# OnStep_Box_SCH.net
KiCad netlist of a schematic drawn in EAGLE
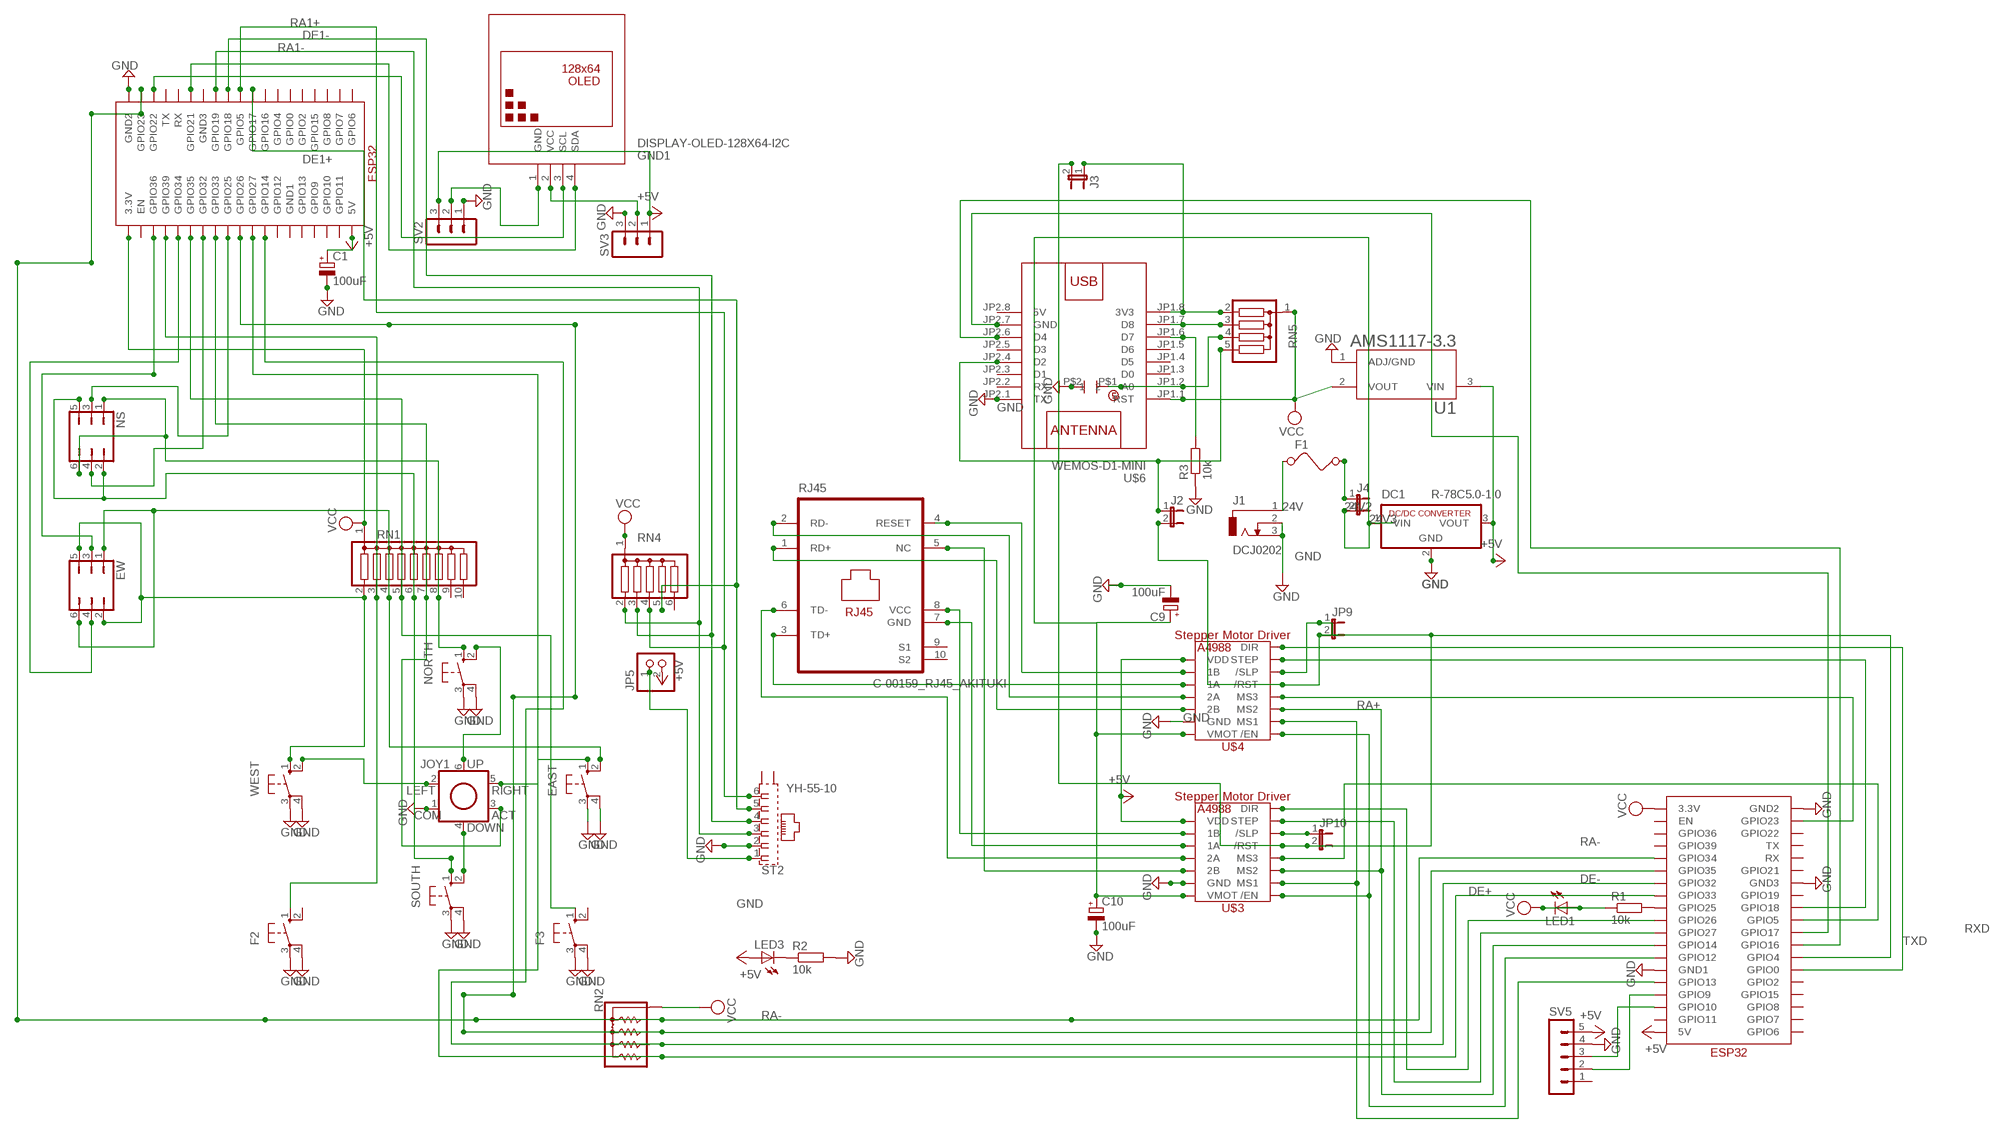
[diagram p0: schematic, sheet 1]

(export (version "E")
  (design (tool "Eeschema 10.0.6"))
  (components
    (comp (ref "C1")
      (value "100uF")
      (footprint "eagle-import:E2-4")
      (libsource (lib "eagle-import") (part "CPOL-EUE2-4"))
    )
    (comp (ref "C9")
      (value "100uF")
      (footprint "eagle-import:E2-5")
      (libsource (lib "eagle-import") (part "rcl_334_CPOL-EUE2-5"))
    )
    (comp (ref "C10")
      (value "100uF")
      (footprint "eagle-import:E2-5")
      (libsource (lib "eagle-import") (part "rcl_334_CPOL-EUE2-5"))
    )
    (comp (ref "CERAMIC_CAPACITOR1")
      (value "CERAMIC_CAPACITOR")
      (footprint "eagle-import:CERAMIC_CAPACITOR")
      (libsource (lib "eagle-import") (part "CERAMIC_CAPACITOR"))
    )
    (comp (ref "DC1")
      (value "R-78C5.0-1.0")
      (footprint "eagle-import:SIP3")
      (libsource (lib "eagle-import") (part "R-78C-1.05.0"))
    )
    (comp (ref "EAST")
      (value "40-XX")
      (footprint "eagle-import:B3F-40XX")
      (fields (field (name "MF") "OMRON COMPONENTS USA") (field (name "MPN") "B3F-4000"))
      (libsource (lib "eagle-import") (part "40-XX"))
    )
    (comp (ref "EW")
      (value "JP3Q")
      (footprint "eagle-import:JP3Q")
      (libsource (lib "eagle-import") (part "JP3Q"))
    )
    (comp (ref "F1")
      (value "FUSE")
      (footprint "eagle-import:FUSE")
      (libsource (lib "eagle-import") (part "FUSE"))
    )
    (comp (ref "F2")
      (value "10-XX")
      (footprint "eagle-import:B3F-10XX")
      (fields (field (name "MPN") "B3F-1000"))
      (libsource (lib "eagle-import") (part "10-XX"))
    )
    (comp (ref "F3")
      (value "10-XX")
      (footprint "eagle-import:B3F-10XX")
      (fields (field (name "MPN") "B3F-1000"))
      (libsource (lib "eagle-import") (part "10-XX"))
    )
    (comp (ref "GND1")
      (value "DISPLAY-OLED-128X64-I2C")
      (footprint "eagle-import:DISPLAY-OLED-128X64-I2C")
      (libsource (lib "eagle-import") (part "DISPLAY-OLED-128X64-I2C"))
    )
    (comp (ref "J1")
      (value "DCJ0202")
      (footprint "eagle-import:DCJ0202")
      (libsource (lib "eagle-import") (part "DCJ0202"))
    )
    (comp (ref "J2")
      (value "JP1E")
      (footprint "eagle-import:JP1")
      (libsource (lib "eagle-import") (part "JP1E"))
    )
    (comp (ref "J3")
      (value "JP1E")
      (footprint "eagle-import:JP1")
      (libsource (lib "eagle-import") (part "JP1E"))
    )
    (comp (ref "J4")
      (value "JP1E")
      (footprint "eagle-import:JP1")
      (libsource (lib "eagle-import") (part "JP1E"))
    )
    (comp (ref "JOY1")
      (value "JOYSTICK")
      (footprint "eagle-import:JOYSTICK")
      (libsource (lib "eagle-import") (part "JOYSTICK"))
    )
    (comp (ref "JP5")
      (value "PINHD-1X2")
      (footprint "eagle-import:1X02")
      (libsource (lib "eagle-import") (part "PINHD-1X2"))
    )
    (comp (ref "JP9")
      (value "JP1E")
      (footprint "eagle-import:JP1")
      (libsource (lib "eagle-import") (part "JP1E"))
    )
    (comp (ref "JP10")
      (value "JP1E")
      (footprint "eagle-import:JP1")
      (libsource (lib "eagle-import") (part "JP1E"))
    )
    (comp (ref "LED1")
      (value "LEDSFH480")
      (footprint "eagle-import:SFH480")
      (libsource (lib "eagle-import") (part "LEDSFH480"))
    )
    (comp (ref "LED3")
      (value "LEDSFH480")
      (footprint "eagle-import:SFH480")
      (libsource (lib "eagle-import") (part "LEDSFH480"))
    )
    (comp (ref "NORTH")
      (value "40-XX")
      (footprint "eagle-import:B3F-40XX")
      (fields (field (name "MF") "OMRON COMPONENTS USA") (field (name "MPN") "B3F-4000"))
      (libsource (lib "eagle-import") (part "40-XX"))
    )
    (comp (ref "NS")
      (value "JP3Q")
      (footprint "eagle-import:JP3Q")
      (libsource (lib "eagle-import") (part "JP3Q"))
    )
    (comp (ref "R1")
      (value "10k")
      (footprint "eagle-import:0204_5")
      (libsource (lib "eagle-import") (part "R-EU_0204/5"))
    )
    (comp (ref "R2")
      (value "10k")
      (footprint "eagle-import:0204_5")
      (libsource (lib "eagle-import") (part "R-EU_0204/5"))
    )
    (comp (ref "R3")
      (value "10k")
      (footprint "eagle-import:0204_5")
      (libsource (lib "eagle-import") (part "R-EU_0204/5"))
    )
    (comp (ref "RJ45")
      (value "C-00159_RJ45_AKITUKI")
      (footprint "eagle-import:PJ-J0")
      (libsource (lib "eagle-import") (part "C-00159_RJ45_AKITUKI"))
    )
    (comp (ref "RN1")
      (value "G09R")
      (footprint "eagle-import:SIL10")
      (libsource (lib "eagle-import") (part "G09R"))
    )
    (comp (ref "RN2")
      (value "4605X")
      (footprint "eagle-import:SIP5")
      (libsource (lib "eagle-import") (part "4605X"))
    )
    (comp (ref "RN4")
      (value "G05R")
      (footprint "eagle-import:SIL6")
      (libsource (lib "eagle-import") (part "G05R"))
    )
    (comp (ref "RN5")
      (value "G04R")
      (footprint "eagle-import:SIL5")
      (libsource (lib "eagle-import") (part "G04R"))
    )
    (comp (ref "SOUTH")
      (value "40-XX")
      (footprint "eagle-import:B3F-40XX")
      (fields (field (name "MF") "OMRON COMPONENTS USA") (field (name "MPN") "B3F-4000"))
      (libsource (lib "eagle-import") (part "40-XX"))
    )
    (comp (ref "ST2")
      (value "YH-55-10")
      (footprint "eagle-import:YH-55-10")
      (libsource (lib "eagle-import") (part "YH-55-10"))
    )
    (comp (ref "SV2")
      (value "MA03-1")
      (footprint "eagle-import:MA03-1")
      (libsource (lib "eagle-import") (part "MA03-1"))
    )
    (comp (ref "SV3")
      (value "MA03-1")
      (footprint "eagle-import:MA03-1")
      (libsource (lib "eagle-import") (part "MA03-1"))
    )
    (comp (ref "SV5")
      (value "MA05-1")
      (footprint "eagle-import:MA05-1")
      (libsource (lib "eagle-import") (part "MA05-1"))
    )
    (comp (ref "U$1")
      (value "ESP32")
      (footprint "eagle-import:ESP32")
      (libsource (lib "eagle-import") (part "ESP32"))
    )
    (comp (ref "U$3")
      (value "A4988_STEP")
      (footprint "eagle-import:A4988_STEP")
      (libsource (lib "eagle-import") (part "A4988_STEP"))
    )
    (comp (ref "U$4")
      (value "A4988_STEP")
      (footprint "eagle-import:A4988_STEP")
      (libsource (lib "eagle-import") (part "A4988_STEP"))
    )
    (comp (ref "U$6")
      (value "WEMOS-D1-MINI")
      (footprint "eagle-import:WEMOS-D1-MINI")
      (libsource (lib "eagle-import") (part "WEMOS-D1-MINI"))
    )
    (comp (ref "U$7")
      (value "ESP32")
      (footprint "eagle-import:ESP32")
      (libsource (lib "eagle-import") (part "ESP32"))
    )
    (comp (ref "U1")
      (value "AMS1117-3.3")
      (footprint "eagle-import:SOT229P700X180-4N")
      (fields (field (name "MF") "Advanced Monolithic Systems"))
      (libsource (lib "eagle-import") (part "AMS1117-3.3"))
    )
    (comp (ref "WEST")
      (value "40-XX")
      (footprint "eagle-import:B3F-40XX")
      (fields (field (name "MF") "OMRON COMPONENTS USA") (field (name "MPN") "B3F-4000"))
      (libsource (lib "eagle-import") (part "40-XX"))
    )
  )
  (nets
    (net (code "1") (name "+5V") (class "Default")
      (node (ref "C1") (pin "+") (pinfunction "+_+") (pintype "passive"))
      (node (ref "DC1") (pin "3") (pinfunction "VOUT_3") (pintype "passive"))
      (node (ref "JP5") (pin "2") (pinfunction "2_2") (pintype "passive"))
      (node (ref "LED3") (pin "A") (pinfunction "A_A") (pintype "passive"))
      (node (ref "SV2") (pin "3") (pinfunction "3_3") (pintype "passive"))
      (node (ref "SV3") (pin "1") (pinfunction "1_1") (pintype "passive"))
      (node (ref "SV5") (pin "5") (pinfunction "5_5") (pintype "passive"))
      (node (ref "U$1") (pin "5V") (pinfunction "5V_5V") (pintype "bidirectional"))
      (node (ref "U$3") (pin "VDD") (pinfunction "VDD_VDD") (pintype "bidirectional"))
      (node (ref "U$4") (pin "VDD") (pinfunction "VDD_VDD") (pintype "bidirectional"))
      (node (ref "U$7") (pin "5V") (pinfunction "5V_5V") (pintype "bidirectional"))
      (node (ref "U1") (pin "3") (pinfunction "VIN_3") (pintype "input"))
    )
    (net (code "2") (name "/5V") (class "Default")
      (node (ref "U$6") (pin "JP2.8") (pinfunction "5V_JP2.8") (pintype "power_in"))
    )
    (net (code "3") (name "/24V") (class "Default")
      (node (ref "F1") (pin "1") (pinfunction "1_1") (pintype "passive"))
      (node (ref "J1") (pin "1") (pinfunction "1_1") (pintype "passive"))
    )
    (net (code "4") (name "/24V2") (class "Default")
      (node (ref "F1") (pin "2") (pinfunction "2_2") (pintype "passive"))
      (node (ref "J4") (pin "1") (pinfunction "1_1") (pintype "passive"))
    )
    (net (code "5") (name "/24V3") (class "Default")
      (node (ref "C10") (pin "+") (pinfunction "+_+") (pintype "passive"))
      (node (ref "C9") (pin "+") (pinfunction "+_+") (pintype "passive"))
      (node (ref "DC1") (pin "1") (pinfunction "VIN_1") (pintype "passive"))
      (node (ref "J4") (pin "2") (pinfunction "2_2") (pintype "passive"))
      (node (ref "U$3") (pin "VMOT") (pinfunction "VMOT_VMOT") (pintype "bidirectional"))
      (node (ref "U$4") (pin "VMOT") (pinfunction "VMOT_VMOT") (pintype "bidirectional"))
    )
    (net (code "6") (name "/DE+") (class "Default")
      (node (ref "RN2") (pin "5") (pinfunction "5_5") (pintype "passive"))
      (node (ref "U$1") (pin "GPIO33") (pinfunction "GPIO33_GPIO33") (pintype "bidirectional"))
      (node (ref "U$7") (pin "GPIO27") (pinfunction "GPIO27_GPIO27") (pintype "bidirectional"))
    )
    (net (code "7") (name "/DE-") (class "Default")
      (node (ref "RN2") (pin "4") (pinfunction "4_4") (pintype "passive"))
      (node (ref "U$1") (pin "GPIO32") (pinfunction "GPIO32_GPIO32") (pintype "bidirectional"))
      (node (ref "U$7") (pin "GPIO14") (pinfunction "GPIO14_GPIO14") (pintype "bidirectional"))
    )
    (net (code "8") (name "/DE1+") (class "Default")
      (node (ref "RN4") (pin "5") (pinfunction "5_5") (pintype "passive"))
      (node (ref "ST2") (pin "5") (pinfunction "5_5") (pintype "passive"))
      (node (ref "U$7") (pin "GPIO17") (pinfunction "GPIO17_GPIO17") (pintype "bidirectional"))
    )
    (net (code "9") (name "/DE1-") (class "Default")
      (node (ref "RN4") (pin "3") (pinfunction "3_3") (pintype "passive"))
      (node (ref "ST2") (pin "4") (pinfunction "4_4") (pintype "passive"))
      (node (ref "U$7") (pin "GPIO18") (pinfunction "GPIO18_GPIO18") (pintype "bidirectional"))
    )
    (net (code "10") (name "/RA+") (class "Default")
      (node (ref "RN2") (pin "3") (pinfunction "3_3") (pintype "passive"))
      (node (ref "U$1") (pin "GPIO35") (pinfunction "GPIO35_GPIO35") (pintype "bidirectional"))
      (node (ref "U$7") (pin "GPIO26") (pinfunction "GPIO26_GPIO26") (pintype "bidirectional"))
    )
    (net (code "11") (name "/RA-") (class "Default")
      (node (ref "RN2") (pin "2") (pinfunction "2_2") (pintype "passive"))
      (node (ref "U$1") (pin "GPIO34") (pinfunction "GPIO34_GPIO34") (pintype "bidirectional"))
      (node (ref "U$7") (pin "GPIO23") (pinfunction "GPIO23_GPIO23") (pintype "bidirectional"))
    )
    (net (code "12") (name "/RA1+") (class "Default")
      (node (ref "RN4") (pin "4") (pinfunction "4_4") (pintype "passive"))
      (node (ref "ST2") (pin "6") (pinfunction "6_6") (pintype "passive"))
      (node (ref "U$7") (pin "GPIO5") (pinfunction "GPIO5_GPIO5") (pintype "bidirectional"))
    )
    (net (code "13") (name "/RA1-") (class "Default")
      (node (ref "RN4") (pin "2") (pinfunction "2_2") (pintype "passive"))
      (node (ref "ST2") (pin "3") (pinfunction "3_3") (pintype "passive"))
      (node (ref "U$7") (pin "GPIO19") (pinfunction "GPIO19_GPIO19") (pintype "bidirectional"))
    )
    (net (code "14") (name "/RXD") (class "Default")
      (node (ref "U$1") (pin "GPIO17") (pinfunction "GPIO17_GPIO17") (pintype "bidirectional"))
      (node (ref "U$6") (pin "JP2.7") (pinfunction "GND_JP2.7") (pintype "power_in"))
    )
    (net (code "15") (name "/TXD") (class "Default")
      (node (ref "U$1") (pin "GPIO16") (pinfunction "GPIO16_GPIO16") (pintype "bidirectional"))
      (node (ref "U$6") (pin "JP2.6") (pinfunction "D4_JP2.6") (pintype "bidirectional"))
    )
    (net (code "16") (name "GND") (class "Default")
      (node (ref "C1") (pin "-") (pinfunction "-_-") (pintype "passive"))
      (node (ref "C10") (pin "-") (pinfunction "-_-") (pintype "passive"))
      (node (ref "C9") (pin "-") (pinfunction "-_-") (pintype "passive"))
      (node (ref "CERAMIC_CAPACITOR1") (pin "P$2") (pinfunction "2_P$2") (pintype "bidirectional"))
      (node (ref "DC1") (pin "2") (pinfunction "GND_2") (pintype "passive"))
      (node (ref "EAST") (pin "3") (pinfunction "P_3") (pintype "passive"))
      (node (ref "EAST") (pin "4") (pinfunction "P1_4") (pintype "passive"))
      (node (ref "F2") (pin "3") (pinfunction "P_3") (pintype "passive"))
      (node (ref "F2") (pin "4") (pinfunction "P1_4") (pintype "passive"))
      (node (ref "F3") (pin "3") (pinfunction "P_3") (pintype "passive"))
      (node (ref "F3") (pin "4") (pinfunction "P1_4") (pintype "passive"))
      (node (ref "J1") (pin "2") (pinfunction "2_2") (pintype "passive"))
      (node (ref "J1") (pin "3") (pinfunction "3_3") (pintype "passive"))
      (node (ref "JOY1") (pin "1") (pinfunction "COM_1") (pintype "bidirectional"))
      (node (ref "NORTH") (pin "3") (pinfunction "P_3") (pintype "passive"))
      (node (ref "NORTH") (pin "4") (pinfunction "P1_4") (pintype "passive"))
      (node (ref "R2") (pin "2") (pinfunction "2_2") (pintype "passive"))
      (node (ref "R3") (pin "1") (pinfunction "1_1") (pintype "passive"))
      (node (ref "SOUTH") (pin "3") (pinfunction "P_3") (pintype "passive"))
      (node (ref "SOUTH") (pin "4") (pinfunction "P1_4") (pintype "passive"))
      (node (ref "ST2") (pin "2") (pinfunction "2_2") (pintype "passive"))
      (node (ref "SV2") (pin "1") (pinfunction "1_1") (pintype "passive"))
      (node (ref "SV3") (pin "3") (pinfunction "3_3") (pintype "passive"))
      (node (ref "SV5") (pin "4") (pinfunction "4_4") (pintype "passive"))
      (node (ref "U$1") (pin "GND1") (pinfunction "GND1_GND1") (pintype "bidirectional"))
      (node (ref "U$1") (pin "GND2") (pinfunction "GND2_GND2") (pintype "bidirectional"))
      (node (ref "U$1") (pin "GND3") (pinfunction "GND3_GND3") (pintype "bidirectional"))
      (node (ref "U$3") (pin "GND") (pinfunction "GND_GND") (pintype "bidirectional"))
      (node (ref "U$3") (pin "GND2") (pinfunction "GND_GND2") (pintype "bidirectional"))
      (node (ref "U$4") (pin "GND") (pinfunction "GND_GND") (pintype "bidirectional"))
      (node (ref "U$4") (pin "GND2") (pinfunction "GND_GND2") (pintype "bidirectional"))
      (node (ref "U$6") (pin "JP2.1") (pinfunction "TX_JP2.1") (pintype "bidirectional"))
      (node (ref "U$7") (pin "GND2") (pinfunction "GND2_GND2") (pintype "bidirectional"))
      (node (ref "U1") (pin "1") (pinfunction "ADJ/GND_1") (pintype "power_in"))
      (node (ref "WEST") (pin "3") (pinfunction "P_3") (pintype "passive"))
      (node (ref "WEST") (pin "4") (pinfunction "P1_4") (pintype "passive"))
    )
    (net (code "17") (name "Net-(CERAMIC_CAPACITOR1-1)") (class "Default")
      (node (ref "CERAMIC_CAPACITOR1") (pin "P$1") (pinfunction "1_P$1") (pintype "bidirectional"))
      (node (ref "RN5") (pin "4") (pinfunction "4_4") (pintype "passive"))
      (node (ref "U$6") (pin "JP1.2") (pinfunction "A0_JP1.2") (pintype "bidirectional"))
    )
    (net (code "18") (name "Net-(EAST-S)") (class "Default")
      (node (ref "EAST") (pin "1") (pinfunction "S_1") (pintype "passive"))
      (node (ref "JOY1") (pin "5") (pinfunction "RIGHT_5") (pintype "bidirectional"))
    )
    (net (code "19") (name "Net-(EAST-S1)") (class "Default")
      (node (ref "EAST") (pin "2") (pinfunction "S1_2") (pintype "passive"))
      (node (ref "EW") (pin "1") (pinfunction "1_1") (pintype "passive"))
      (node (ref "EW") (pin "6") (pinfunction "6_6") (pintype "passive"))
      (node (ref "RN1") (pin "4") (pinfunction "4_4") (pintype "passive"))
    )
    (net (code "20") (name "Net-(EW-Pad3)") (class "Default")
      (node (ref "EW") (pin "3") (pinfunction "3_3") (pintype "passive"))
      (node (ref "U$7") (pin "GPIO36") (pinfunction "GPIO36_GPIO36") (pintype "bidirectional"))
    )
    (net (code "21") (name "Net-(EW-Pad4)") (class "Default")
      (node (ref "EW") (pin "4") (pinfunction "4_4") (pintype "passive"))
      (node (ref "U$7") (pin "GPIO34") (pinfunction "GPIO34_GPIO34") (pintype "bidirectional"))
    )
    (net (code "22") (name "Net-(F2-S)") (class "Default")
      (node (ref "F2") (pin "1") (pinfunction "S_1") (pintype "passive"))
      (node (ref "RN1") (pin "3") (pinfunction "3_3") (pintype "passive"))
      (node (ref "U$7") (pin "GPIO39") (pinfunction "GPIO39_GPIO39") (pintype "bidirectional"))
    )
    (net (code "23") (name "Net-(F3-S)") (class "Default")
      (node (ref "F3") (pin "1") (pinfunction "S_1") (pintype "passive"))
      (node (ref "RN1") (pin "5") (pinfunction "5_5") (pintype "passive"))
      (node (ref "U$7") (pin "GPIO35") (pinfunction "GPIO35_GPIO35") (pintype "bidirectional"))
    )
    (net (code "24") (name "Net-(GND1-GND)") (class "Default")
      (node (ref "GND1") (pin "1") (pinfunction "GND_1") (pintype "power_in"))
      (node (ref "SV2") (pin "2") (pinfunction "2_2") (pintype "passive"))
    )
    (net (code "25") (name "Net-(GND1-SCL)") (class "Default")
      (node (ref "GND1") (pin "3") (pinfunction "SCL_3") (pintype "bidirectional"))
      (node (ref "U$7") (pin "GPIO22") (pinfunction "GPIO22_GPIO22") (pintype "bidirectional"))
    )
    (net (code "26") (name "Net-(GND1-SDA)") (class "Default")
      (node (ref "GND1") (pin "4") (pinfunction "SDA_4") (pintype "bidirectional"))
      (node (ref "U$7") (pin "GPIO21") (pinfunction "GPIO21_GPIO21") (pintype "bidirectional"))
    )
    (net (code "27") (name "Net-(GND1-VCC)") (class "Default")
      (node (ref "GND1") (pin "2") (pinfunction "VCC_2") (pintype "power_in"))
      (node (ref "SV3") (pin "2") (pinfunction "2_2") (pintype "passive"))
    )
    (net (code "28") (name "Net-(J2-Pad2)") (class "Default")
      (node (ref "J2") (pin "2") (pinfunction "2_2") (pintype "passive"))
      (node (ref "J3") (pin "2") (pinfunction "2_2") (pintype "passive"))
      (node (ref "JP10") (pin "2") (pinfunction "2_2") (pintype "passive"))
      (node (ref "JP9") (pin "1") (pinfunction "1_1") (pintype "passive"))
      (node (ref "JP9") (pin "2") (pinfunction "2_2") (pintype "passive"))
      (node (ref "U$1") (pin "GPIO4") (pinfunction "GPIO4_GPIO4") (pintype "bidirectional"))
      (node (ref "U$3") (pin "/RST") (pinfunction "/RST_/RST") (pintype "bidirectional"))
      (node (ref "U$4") (pin "/RST") (pinfunction "/RST_/RST") (pintype "bidirectional"))
      (node (ref "U$4") (pin "/SLP") (pinfunction "/SLP_/SLP") (pintype "bidirectional"))
    )
    (net (code "29") (name "Net-(JOY1-ACT)") (class "Default")
      (node (ref "JOY1") (pin "3") (pinfunction "ACT_3") (pintype "bidirectional"))
      (node (ref "RN1") (pin "7") (pinfunction "7_7") (pintype "passive"))
      (node (ref "U$7") (pin "GPIO33") (pinfunction "GPIO33_GPIO33") (pintype "bidirectional"))
    )
    (net (code "30") (name "Net-(JOY1-DOWN)") (class "Default")
      (node (ref "JOY1") (pin "4") (pinfunction "DOWN_4") (pintype "bidirectional"))
      (node (ref "SOUTH") (pin "2") (pinfunction "S1_2") (pintype "passive"))
    )
    (net (code "31") (name "Net-(JOY1-LEFT)") (class "Default")
      (node (ref "JOY1") (pin "2") (pinfunction "LEFT_2") (pintype "bidirectional"))
      (node (ref "WEST") (pin "2") (pinfunction "S1_2") (pintype "passive"))
    )
    (net (code "32") (name "Net-(JOY1-UP)") (class "Default")
      (node (ref "JOY1") (pin "6") (pinfunction "UP_6") (pintype "bidirectional"))
      (node (ref "NORTH") (pin "2") (pinfunction "S1_2") (pintype "passive"))
    )
    (net (code "33") (name "Net-(JP5-Pad1)") (class "Default")
      (node (ref "JP5") (pin "1") (pinfunction "1_1") (pintype "passive"))
      (node (ref "ST2") (pin "1") (pinfunction "1_1") (pintype "passive"))
    )
    (net (code "34") (name "Net-(JP10-Pad1)") (class "Default")
      (node (ref "JP10") (pin "1") (pinfunction "1_1") (pintype "passive"))
      (node (ref "U$3") (pin "/SLP") (pinfunction "/SLP_/SLP") (pintype "bidirectional"))
    )
    (net (code "35") (name "Net-(LED3-C)") (class "Default")
      (node (ref "LED3") (pin "K") (pinfunction "C_K") (pintype "passive"))
      (node (ref "R2") (pin "1") (pinfunction "1_1") (pintype "passive"))
    )
    (net (code "36") (name "Net-(NORTH-S)") (class "Default")
      (node (ref "NORTH") (pin "1") (pinfunction "S_1") (pintype "passive"))
      (node (ref "NS") (pin "1") (pinfunction "1_1") (pintype "passive"))
      (node (ref "NS") (pin "6") (pinfunction "6_6") (pintype "passive"))
      (node (ref "RN1") (pin "8") (pinfunction "8_8") (pintype "passive"))
    )
    (net (code "37") (name "Net-(NS-Pad3)") (class "Default")
      (node (ref "NS") (pin "3") (pinfunction "3_3") (pintype "passive"))
      (node (ref "U$7") (pin "GPIO25") (pinfunction "GPIO25_GPIO25") (pintype "bidirectional"))
    )
    (net (code "38") (name "Net-(NS-Pad4)") (class "Default")
      (node (ref "NS") (pin "4") (pinfunction "4_4") (pintype "passive"))
      (node (ref "U$7") (pin "GPIO32") (pinfunction "GPIO32_GPIO32") (pintype "bidirectional"))
    )
    (net (code "39") (name "Net-(R1-Pad2)") (class "Default")
      (node (ref "R1") (pin "2") (pinfunction "2_2") (pintype "passive"))
      (node (ref "U$1") (pin "GPIO25") (pinfunction "GPIO25_GPIO25") (pintype "bidirectional"))
    )
    (net (code "40") (name "Net-(RJ45-GND)") (class "Default")
      (node (ref "RJ45") (pin "7") (pinfunction "GND_7") (pintype "passive"))
      (node (ref "U$3") (pin "1A") (pinfunction "1A_1A") (pintype "bidirectional"))
    )
    (net (code "41") (name "Net-(RJ45-NC)") (class "Default")
      (node (ref "RJ45") (pin "5") (pinfunction "NC_5") (pintype "bidirectional"))
      (node (ref "U$3") (pin "2B") (pinfunction "2B_2B") (pintype "bidirectional"))
    )
    (net (code "42") (name "Net-(RJ45-RD+)") (class "Default")
      (node (ref "RJ45") (pin "1") (pinfunction "RD+_1") (pintype "bidirectional"))
      (node (ref "U$4") (pin "2B") (pinfunction "2B_2B") (pintype "bidirectional"))
    )
    (net (code "43") (name "Net-(RJ45-RD-)") (class "Default")
      (node (ref "RJ45") (pin "2") (pinfunction "RD-_2") (pintype "bidirectional"))
      (node (ref "U$4") (pin "2A") (pinfunction "2A_2A") (pintype "bidirectional"))
    )
    (net (code "44") (name "Net-(RJ45-RESET)") (class "Default")
      (node (ref "RJ45") (pin "4") (pinfunction "RESET_4") (pintype "bidirectional"))
      (node (ref "U$4") (pin "1B") (pinfunction "1B_1B") (pintype "bidirectional"))
    )
    (net (code "45") (name "Net-(RJ45-TD+)") (class "Default")
      (node (ref "RJ45") (pin "3") (pinfunction "TD+_3") (pintype "bidirectional"))
      (node (ref "U$4") (pin "1A") (pinfunction "1A_1A") (pintype "bidirectional"))
    )
    (net (code "46") (name "Net-(RJ45-TD-)") (class "Default")
      (node (ref "RJ45") (pin "6") (pinfunction "TD-_6") (pintype "bidirectional"))
      (node (ref "U$3") (pin "2A") (pinfunction "2A_2A") (pintype "bidirectional"))
    )
    (net (code "47") (name "Net-(RJ45-VCC)") (class "Default")
      (node (ref "RJ45") (pin "8") (pinfunction "VCC_8") (pintype "passive"))
      (node (ref "U$3") (pin "1B") (pinfunction "1B_1B") (pintype "bidirectional"))
    )
    (net (code "48") (name "Net-(SOUTH-S)") (class "Default")
      (node (ref "NS") (pin "2") (pinfunction "2_2") (pintype "passive"))
      (node (ref "NS") (pin "5") (pinfunction "5_5") (pintype "passive"))
      (node (ref "RN1") (pin "6") (pinfunction "6_6") (pintype "passive"))
      (node (ref "SOUTH") (pin "1") (pinfunction "S_1") (pintype "passive"))
    )
    (net (code "49") (name "Net-(SV5-Pad2)") (class "Default")
      (node (ref "SV5") (pin "2") (pinfunction "2_2") (pintype "passive"))
      (node (ref "U$1") (pin "GPIO9") (pinfunction "GPIO9_GPIO9") (pintype "bidirectional"))
    )
    (net (code "50") (name "Net-(SV5-Pad3)") (class "Default")
      (node (ref "SV5") (pin "3") (pinfunction "3_3") (pintype "passive"))
      (node (ref "U$1") (pin "GPIO10") (pinfunction "GPIO10_GPIO10") (pintype "bidirectional"))
    )
    (net (code "51") (name "Net-(U$1-PadGPIO0)") (class "Default")
      (node (ref "U$1") (pin "GPIO0") (pinfunction "GPIO0_GPIO0") (pintype "bidirectional"))
      (node (ref "U$4") (pin "DIR") (pinfunction "DIR_DIR") (pintype "bidirectional"))
    )
    (net (code "52") (name "Net-(U$1-PadGPIO5)") (class "Default")
      (node (ref "U$1") (pin "GPIO5") (pinfunction "GPIO5_GPIO5") (pintype "bidirectional"))
      (node (ref "U$3") (pin "MS3") (pinfunction "MS3_MS3") (pintype "bidirectional"))
    )
    (net (code "53") (name "Net-(U$1-PadGPIO12)") (class "Default")
      (node (ref "U$1") (pin "GPIO12") (pinfunction "GPIO12_GPIO12") (pintype "bidirectional"))
      (node (ref "U$3") (pin "/EN") (pinfunction "/EN_/EN") (pintype "bidirectional"))
      (node (ref "U$4") (pin "/EN") (pinfunction "/EN_/EN") (pintype "bidirectional"))
    )
    (net (code "54") (name "Net-(U$1-PadGPIO13)") (class "Default")
      (node (ref "U$1") (pin "GPIO13") (pinfunction "GPIO13_GPIO13") (pintype "bidirectional"))
      (node (ref "U$3") (pin "MS1") (pinfunction "MS1_MS1") (pintype "bidirectional"))
      (node (ref "U$4") (pin "MS1") (pinfunction "MS1_MS1") (pintype "bidirectional"))
    )
    (net (code "55") (name "Net-(U$1-PadGPIO14)") (class "Default")
      (node (ref "U$1") (pin "GPIO14") (pinfunction "GPIO14_GPIO14") (pintype "bidirectional"))
      (node (ref "U$3") (pin "MS2") (pinfunction "MS2_MS2") (pintype "bidirectional"))
      (node (ref "U$4") (pin "MS2") (pinfunction "MS2_MS2") (pintype "bidirectional"))
    )
    (net (code "56") (name "Net-(U$1-PadGPIO18)") (class "Default")
      (node (ref "U$1") (pin "GPIO18") (pinfunction "GPIO18_GPIO18") (pintype "bidirectional"))
      (node (ref "U$4") (pin "STEP") (pinfunction "STEP_STEP") (pintype "bidirectional"))
    )
    (net (code "57") (name "Net-(U$1-PadGPIO23)") (class "Default")
      (node (ref "U$1") (pin "GPIO23") (pinfunction "GPIO23_GPIO23") (pintype "bidirectional"))
      (node (ref "U$4") (pin "MS3") (pinfunction "MS3_MS3") (pintype "bidirectional"))
    )
    (net (code "58") (name "Net-(U$1-PadGPIO26)") (class "Default")
      (node (ref "U$1") (pin "GPIO26") (pinfunction "GPIO26_GPIO26") (pintype "bidirectional"))
      (node (ref "U$3") (pin "DIR") (pinfunction "DIR_DIR") (pintype "bidirectional"))
    )
    (net (code "59") (name "Net-(U$1-PadGPIO27)") (class "Default")
      (node (ref "U$1") (pin "GPIO27") (pinfunction "GPIO27_GPIO27") (pintype "bidirectional"))
      (node (ref "U$3") (pin "STEP") (pinfunction "STEP_STEP") (pintype "bidirectional"))
    )
    (net (code "60") (name "Net-(U$6-3V3)") (class "Default")
      (node (ref "J3") (pin "1") (pinfunction "1_1") (pintype "passive"))
      (node (ref "RN5") (pin "2") (pinfunction "2_2") (pintype "passive"))
      (node (ref "U$6") (pin "JP1.8") (pinfunction "3V3_JP1.8") (pintype "power_in"))
    )
    (net (code "61") (name "Net-(U$6-D2)") (class "Default")
      (node (ref "J2") (pin "1") (pinfunction "1_1") (pintype "passive"))
      (node (ref "RN5") (pin "5") (pinfunction "5_5") (pintype "passive"))
      (node (ref "U$6") (pin "JP2.4") (pinfunction "D2_JP2.4") (pintype "bidirectional"))
    )
    (net (code "62") (name "Net-(U$6-D7)") (class "Default")
      (node (ref "R3") (pin "2") (pinfunction "2_2") (pintype "passive"))
      (node (ref "U$6") (pin "JP1.6") (pinfunction "D7_JP1.6") (pintype "bidirectional"))
    )
    (net (code "63") (name "Net-(U$6-D8)") (class "Default")
      (node (ref "RN5") (pin "3") (pinfunction "3_3") (pintype "passive"))
      (node (ref "U$6") (pin "JP1.7") (pinfunction "D8_JP1.7") (pintype "bidirectional"))
    )
    (net (code "64") (name "Net-(WEST-S)") (class "Default")
      (node (ref "EW") (pin "2") (pinfunction "2_2") (pintype "passive"))
      (node (ref "EW") (pin "5") (pinfunction "5_5") (pintype "passive"))
      (node (ref "RN1") (pin "2") (pinfunction "2_2") (pintype "passive"))
      (node (ref "WEST") (pin "1") (pinfunction "S_1") (pintype "passive"))
    )
    (net (code "65") (name "VCC") (class "Default")
      (node (ref "LED1") (pin "A") (pinfunction "A_A") (pintype "passive"))
      (node (ref "LED1") (pin "K") (pinfunction "C_K") (pintype "passive"))
      (node (ref "R1") (pin "1") (pinfunction "1_1") (pintype "passive"))
      (node (ref "RN1") (pin "1") (pinfunction "1_1") (pintype "passive"))
      (node (ref "RN2") (pin "1") (pinfunction "1_1") (pintype "passive"))
      (node (ref "RN4") (pin "1") (pinfunction "1_1") (pintype "passive"))
      (node (ref "RN5") (pin "1") (pinfunction "1_1") (pintype "passive"))
      (node (ref "U$1") (pin "3.3V") (pinfunction "3.3V_3.3V") (pintype "bidirectional"))
      (node (ref "U$6") (pin "JP1.1") (pinfunction "RST_JP1.1") (pintype "bidirectional"))
      (node (ref "U$7") (pin "3.3V") (pinfunction "3.3V_3.3V") (pintype "bidirectional"))
      (node (ref "U1") (pin "2") (pinfunction "VOUT_2") (pintype "output"))
    )
    (net (code "66") (name "unconnected-(F2-S1-Pad2)") (class "Default")
      (node (ref "F2") (pin "2") (pinfunction "S1_2") (pintype "passive"))
    )
    (net (code "67") (name "unconnected-(F3-S1-Pad2)") (class "Default")
      (node (ref "F3") (pin "2") (pinfunction "S1_2") (pintype "passive"))
    )
    (net (code "68") (name "unconnected-(RJ45-S1-Pad9)") (class "Default")
      (node (ref "RJ45") (pin "9") (pinfunction "S1_9") (pintype "passive"))
    )
    (net (code "69") (name "unconnected-(RJ45-S2-Pad10)") (class "Default")
      (node (ref "RJ45") (pin "10") (pinfunction "S2_10") (pintype "passive"))
    )
    (net (code "70") (name "unconnected-(RN1-Pad9)") (class "Default")
      (node (ref "RN1") (pin "9") (pinfunction "9_9") (pintype "passive"))
    )
    (net (code "71") (name "unconnected-(RN1-Pad10)") (class "Default")
      (node (ref "RN1") (pin "10") (pinfunction "10_10") (pintype "passive"))
    )
    (net (code "72") (name "unconnected-(RN4-Pad6)") (class "Default")
      (node (ref "RN4") (pin "6") (pinfunction "6_6") (pintype "passive"))
    )
    (net (code "73") (name "unconnected-(ST2-S-PadS1)") (class "Default")
      (node (ref "ST2") (pin "S1") (pinfunction "S_S1") (pintype "passive"))
    )
    (net (code "74") (name "unconnected-(ST2-S-PadS2)") (class "Default")
      (node (ref "ST2") (pin "S2") (pinfunction "S_S2") (pintype "passive"))
    )
    (net (code "75") (name "unconnected-(SV5-Pad1)") (class "Default")
      (node (ref "SV5") (pin "1") (pinfunction "1_1") (pintype "passive"))
    )
    (net (code "76") (name "unconnected-(U$1-PadEN)") (class "Default")
      (node (ref "U$1") (pin "EN") (pinfunction "EN_EN") (pintype "bidirectional"))
    )
    (net (code "77") (name "unconnected-(U$1-PadGPIO2)") (class "Default")
      (node (ref "U$1") (pin "GPIO2") (pinfunction "GPIO2_GPIO2") (pintype "bidirectional"))
    )
    (net (code "78") (name "unconnected-(U$1-PadGPIO6)") (class "Default")
      (node (ref "U$1") (pin "GPIO6") (pinfunction "GPIO6_GPIO6") (pintype "bidirectional"))
    )
    (net (code "79") (name "unconnected-(U$1-PadGPIO7)") (class "Default")
      (node (ref "U$1") (pin "GPIO7") (pinfunction "GPIO7_GPIO7") (pintype "bidirectional"))
    )
    (net (code "80") (name "unconnected-(U$1-PadGPIO8)") (class "Default")
      (node (ref "U$1") (pin "GPIO8") (pinfunction "GPIO8_GPIO8") (pintype "bidirectional"))
    )
    (net (code "81") (name "unconnected-(U$1-PadGPIO11)") (class "Default")
      (node (ref "U$1") (pin "GPIO11") (pinfunction "GPIO11_GPIO11") (pintype "bidirectional"))
    )
    (net (code "82") (name "unconnected-(U$1-PadGPIO15)") (class "Default")
      (node (ref "U$1") (pin "GPIO15") (pinfunction "GPIO15_GPIO15") (pintype "bidirectional"))
    )
    (net (code "83") (name "unconnected-(U$1-PadGPIO19)") (class "Default")
      (node (ref "U$1") (pin "GPIO19") (pinfunction "GPIO19_GPIO19") (pintype "bidirectional"))
    )
    (net (code "84") (name "unconnected-(U$1-PadGPIO21)") (class "Default")
      (node (ref "U$1") (pin "GPIO21") (pinfunction "GPIO21_GPIO21") (pintype "bidirectional"))
    )
    (net (code "85") (name "unconnected-(U$1-PadGPIO22)") (class "Default")
      (node (ref "U$1") (pin "GPIO22") (pinfunction "GPIO22_GPIO22") (pintype "bidirectional"))
    )
    (net (code "86") (name "unconnected-(U$1-PadGPIO36)") (class "Default")
      (node (ref "U$1") (pin "GPIO36") (pinfunction "GPIO36_GPIO36") (pintype "bidirectional"))
    )
    (net (code "87") (name "unconnected-(U$1-PadGPIO39)") (class "Default")
      (node (ref "U$1") (pin "GPIO39") (pinfunction "GPIO39_GPIO39") (pintype "bidirectional"))
    )
    (net (code "88") (name "unconnected-(U$1-PadRX)") (class "Default")
      (node (ref "U$1") (pin "RX") (pinfunction "RX_RX") (pintype "bidirectional"))
    )
    (net (code "89") (name "unconnected-(U$1-PadTX)") (class "Default")
      (node (ref "U$1") (pin "TX") (pinfunction "TX_TX") (pintype "bidirectional"))
    )
    (net (code "90") (name "unconnected-(U$6-D0-PadJP1.3)") (class "Default")
      (node (ref "U$6") (pin "JP1.3") (pinfunction "D0_JP1.3") (pintype "bidirectional"))
    )
    (net (code "91") (name "unconnected-(U$6-D1-PadJP2.3)") (class "Default")
      (node (ref "U$6") (pin "JP2.3") (pinfunction "D1_JP2.3") (pintype "bidirectional"))
    )
    (net (code "92") (name "unconnected-(U$6-D3-PadJP2.5)") (class "Default")
      (node (ref "U$6") (pin "JP2.5") (pinfunction "D3_JP2.5") (pintype "bidirectional"))
    )
    (net (code "93") (name "unconnected-(U$6-D5-PadJP1.4)") (class "Default")
      (node (ref "U$6") (pin "JP1.4") (pinfunction "D5_JP1.4") (pintype "bidirectional"))
    )
    (net (code "94") (name "unconnected-(U$6-D6-PadJP1.5)") (class "Default")
      (node (ref "U$6") (pin "JP1.5") (pinfunction "D6_JP1.5") (pintype "bidirectional"))
    )
    (net (code "95") (name "unconnected-(U$6-RX-PadJP2.2)") (class "Default")
      (node (ref "U$6") (pin "JP2.2") (pinfunction "RX_JP2.2") (pintype "bidirectional"))
    )
    (net (code "96") (name "unconnected-(U$7-PadEN)") (class "Default")
      (node (ref "U$7") (pin "EN") (pinfunction "EN_EN") (pintype "bidirectional"))
    )
    (net (code "97") (name "unconnected-(U$7-PadGND1)") (class "Default")
      (node (ref "U$7") (pin "GND1") (pinfunction "GND1_GND1") (pintype "bidirectional"))
    )
    (net (code "98") (name "unconnected-(U$7-PadGND3)") (class "Default")
      (node (ref "U$7") (pin "GND3") (pinfunction "GND3_GND3") (pintype "bidirectional"))
    )
    (net (code "99") (name "unconnected-(U$7-PadGPIO0)") (class "Default")
      (node (ref "U$7") (pin "GPIO0") (pinfunction "GPIO0_GPIO0") (pintype "bidirectional"))
    )
    (net (code "100") (name "unconnected-(U$7-PadGPIO2)") (class "Default")
      (node (ref "U$7") (pin "GPIO2") (pinfunction "GPIO2_GPIO2") (pintype "bidirectional"))
    )
    (net (code "101") (name "unconnected-(U$7-PadGPIO4)") (class "Default")
      (node (ref "U$7") (pin "GPIO4") (pinfunction "GPIO4_GPIO4") (pintype "bidirectional"))
    )
    (net (code "102") (name "unconnected-(U$7-PadGPIO6)") (class "Default")
      (node (ref "U$7") (pin "GPIO6") (pinfunction "GPIO6_GPIO6") (pintype "bidirectional"))
    )
    (net (code "103") (name "unconnected-(U$7-PadGPIO7)") (class "Default")
      (node (ref "U$7") (pin "GPIO7") (pinfunction "GPIO7_GPIO7") (pintype "bidirectional"))
    )
    (net (code "104") (name "unconnected-(U$7-PadGPIO8)") (class "Default")
      (node (ref "U$7") (pin "GPIO8") (pinfunction "GPIO8_GPIO8") (pintype "bidirectional"))
    )
    (net (code "105") (name "unconnected-(U$7-PadGPIO9)") (class "Default")
      (node (ref "U$7") (pin "GPIO9") (pinfunction "GPIO9_GPIO9") (pintype "bidirectional"))
    )
    (net (code "106") (name "unconnected-(U$7-PadGPIO10)") (class "Default")
      (node (ref "U$7") (pin "GPIO10") (pinfunction "GPIO10_GPIO10") (pintype "bidirectional"))
    )
    (net (code "107") (name "unconnected-(U$7-PadGPIO11)") (class "Default")
      (node (ref "U$7") (pin "GPIO11") (pinfunction "GPIO11_GPIO11") (pintype "bidirectional"))
    )
    (net (code "108") (name "unconnected-(U$7-PadGPIO12)") (class "Default")
      (node (ref "U$7") (pin "GPIO12") (pinfunction "GPIO12_GPIO12") (pintype "bidirectional"))
    )
    (net (code "109") (name "unconnected-(U$7-PadGPIO13)") (class "Default")
      (node (ref "U$7") (pin "GPIO13") (pinfunction "GPIO13_GPIO13") (pintype "bidirectional"))
    )
    (net (code "110") (name "unconnected-(U$7-PadGPIO15)") (class "Default")
      (node (ref "U$7") (pin "GPIO15") (pinfunction "GPIO15_GPIO15") (pintype "bidirectional"))
    )
    (net (code "111") (name "unconnected-(U$7-PadGPIO16)") (class "Default")
      (node (ref "U$7") (pin "GPIO16") (pinfunction "GPIO16_GPIO16") (pintype "bidirectional"))
    )
    (net (code "112") (name "unconnected-(U$7-PadRX)") (class "Default")
      (node (ref "U$7") (pin "RX") (pinfunction "RX_RX") (pintype "bidirectional"))
    )
    (net (code "113") (name "unconnected-(U$7-PadTX)") (class "Default")
      (node (ref "U$7") (pin "TX") (pinfunction "TX_TX") (pintype "bidirectional"))
    )
  )
)
